# BMS_AFE_-_AFE.net
KiCad netlist of a schematic drawn in Altium Designer
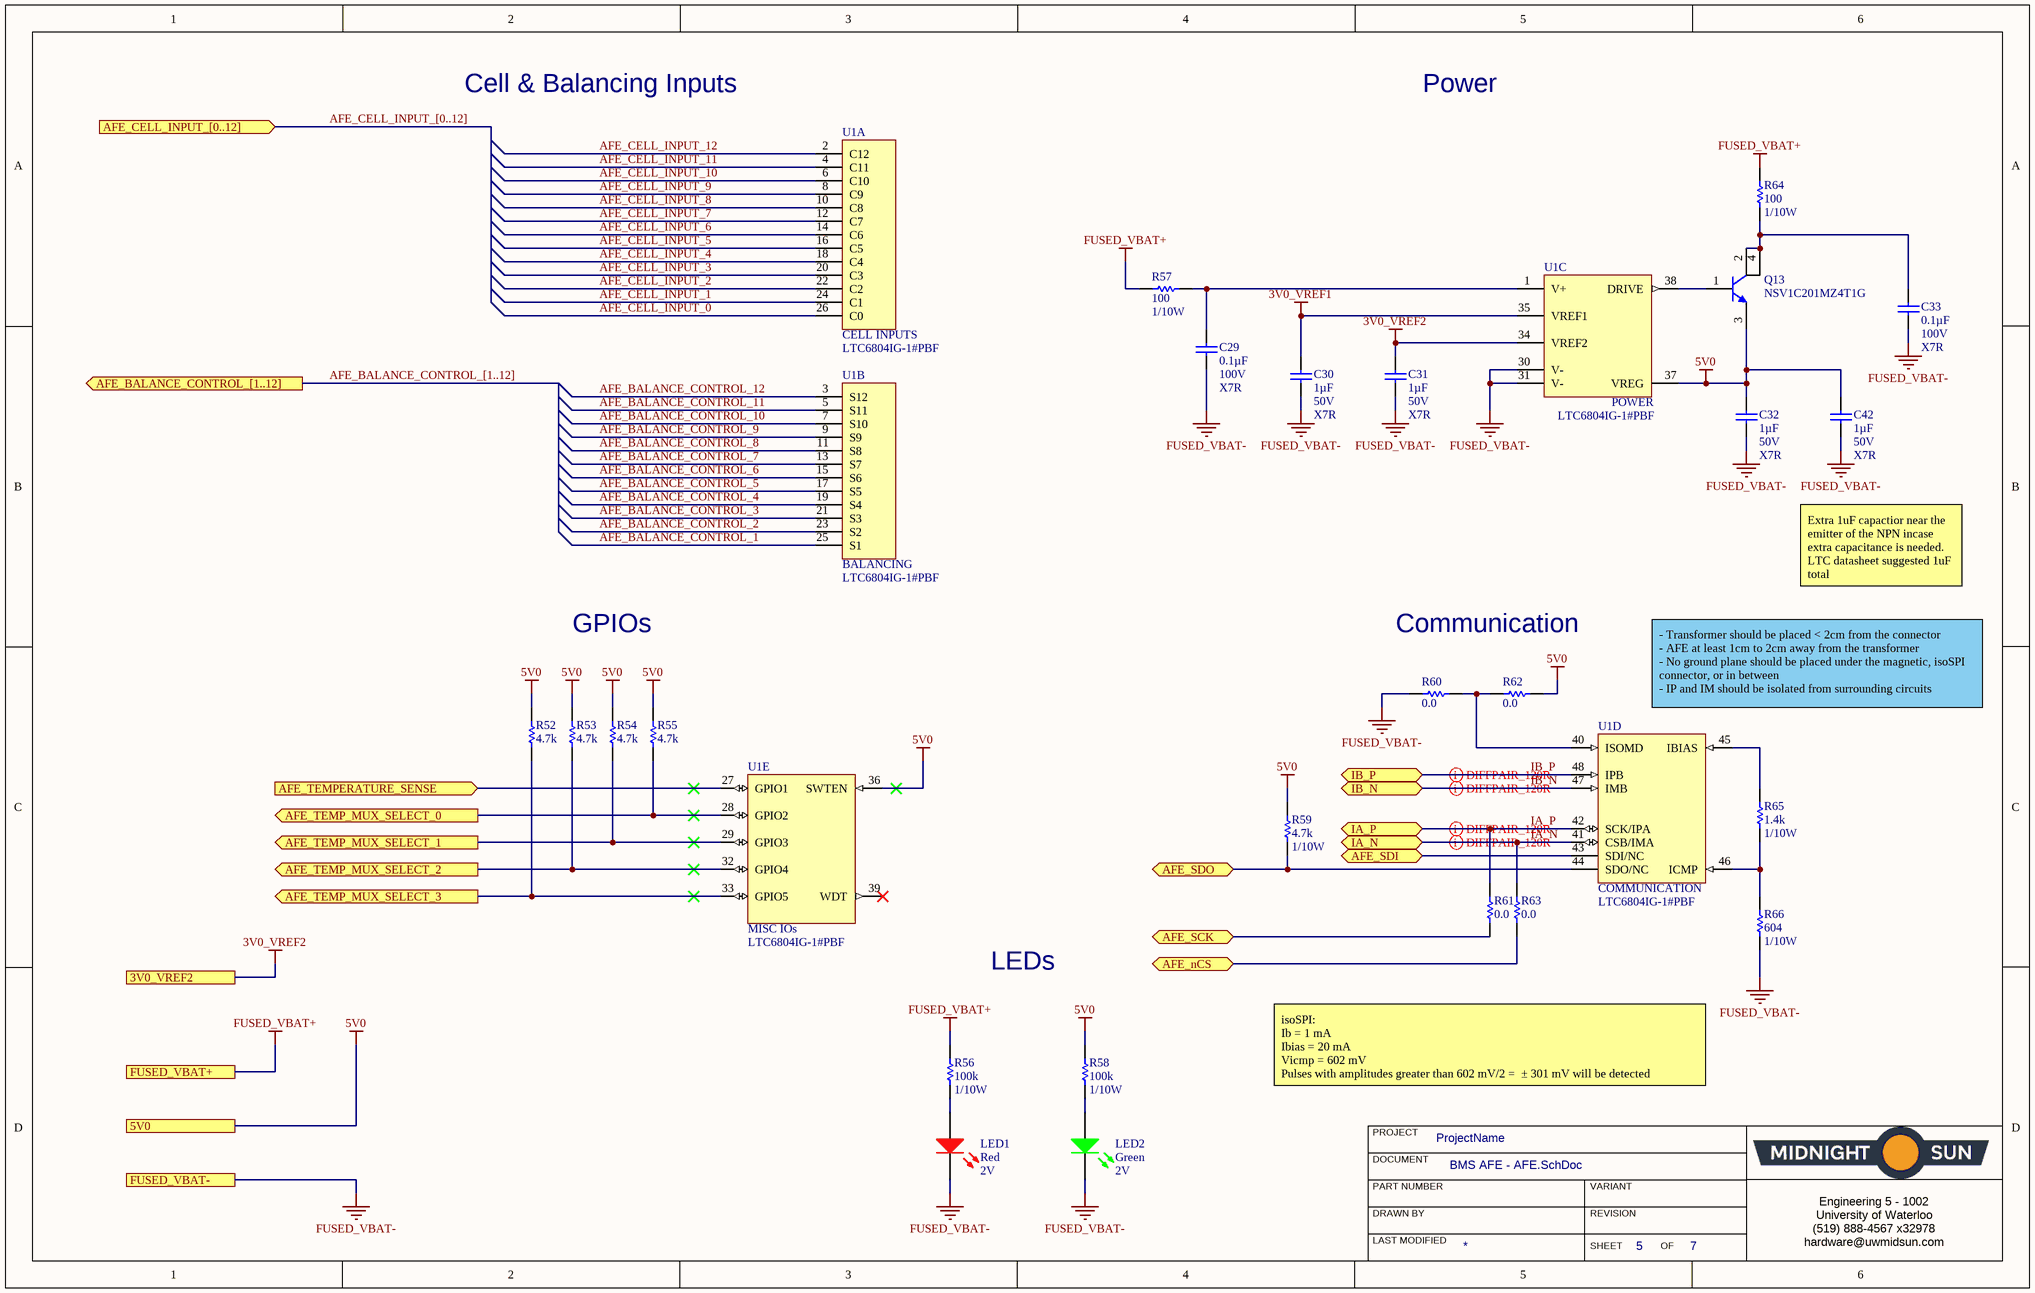
[diagram p0: BMS AFE - AFE.SchDoc]

(export (version "E")
  (design (tool "Eeschema 10.0.6"))
  (components
    (comp (ref "C29")
      (value "CAP CER 0.1UF 100V 10% X7R 0805")
      (footprint "CAP, 0805")
      (description "0.1µF ±10% 100V Ceramic Capacitor X7R 0805 (2012 Metric)")
      (fields
        (field (name "TOLERANCE") "±10%")
        (field (name "CAPACITANCE") "0.1µF")
        (field (name "VOLTAGE") "100V")
        (field (name "TEMPERATURE COEFFICIENT") "X7R")
      )
      (libsource (lib "Schematic Diagrams") (part "CAP CER 0.1UF 100V 10% X7R 0805"))
    )
    (comp (ref "C30")
      (value "CAP CER 1UF 50V 10% X7R 0603")
      (footprint "CAP, 0603")
      (description "1µF ±10% 50V Ceramic Capacitor X7R 0603 (1608 Metric)")
      (fields
        (field (name "TOLERANCE") "±10%")
        (field (name "CAPACITANCE") "1µF")
        (field (name "VOLTAGE") "50V")
        (field (name "TEMPERATURE COEFFICIENT") "X7R")
      )
      (libsource (lib "Schematic Diagrams") (part "CAP CER 1UF 50V 10% X7R 0603"))
    )
    (comp (ref "C31")
      (value "CAP CER 1UF 50V 10% X7R 0603")
      (footprint "CAP, 0603")
      (description "1µF ±10% 50V Ceramic Capacitor X7R 0603 (1608 Metric)")
      (fields
        (field (name "TOLERANCE") "±10%")
        (field (name "CAPACITANCE") "1µF")
        (field (name "VOLTAGE") "50V")
        (field (name "TEMPERATURE COEFFICIENT") "X7R")
      )
      (libsource (lib "Schematic Diagrams") (part "CAP CER 1UF 50V 10% X7R 0603"))
    )
    (comp (ref "C32")
      (value "CAP CER 1UF 50V 10% X7R 0603")
      (footprint "CAP, 0603")
      (description "1µF ±10% 50V Ceramic Capacitor X7R 0603 (1608 Metric)")
      (fields
        (field (name "TOLERANCE") "±10%")
        (field (name "CAPACITANCE") "1µF")
        (field (name "VOLTAGE") "50V")
        (field (name "TEMPERATURE COEFFICIENT") "X7R")
      )
      (libsource (lib "Schematic Diagrams") (part "CAP CER 1UF 50V 10% X7R 0603"))
    )
    (comp (ref "C33")
      (value "CAP CER 0.1UF 100V 10% X7R 0805")
      (footprint "CAP, 0805")
      (description "0.1µF ±10% 100V Ceramic Capacitor X7R 0805 (2012 Metric)")
      (fields
        (field (name "TOLERANCE") "±10%")
        (field (name "CAPACITANCE") "0.1µF")
        (field (name "VOLTAGE") "100V")
        (field (name "TEMPERATURE COEFFICIENT") "X7R")
      )
      (libsource (lib "Schematic Diagrams") (part "CAP CER 0.1UF 100V 10% X7R 0805"))
    )
    (comp (ref "C42")
      (value "CAP CER 1UF 50V 10% X7R 0603")
      (footprint "CAP, 0603")
      (description "1µF ±10% 50V Ceramic Capacitor X7R 0603 (1608 Metric)")
      (fields
        (field (name "TOLERANCE") "±10%")
        (field (name "CAPACITANCE") "1µF")
        (field (name "VOLTAGE") "50V")
        (field (name "TEMPERATURE COEFFICIENT") "X7R")
      )
      (libsource (lib "Schematic Diagrams") (part "CAP CER 1UF 50V 10% X7R 0603"))
    )
    (comp (ref "LED1")
      (value "LED RED CLEAR 2V 0603")
      (footprint "LED_0603")
      (description "Red 631nm LED Indication - Discrete 2V 0603 (1608 Metric)")
      (fields
        (field (name "MANUFACTURER") "Wurth Electronics Inc.")
        (field (name "MANUFACTURER PART NUMBER") "150060RS75000")
        (field (name "COLOR") "Red")
        (field (name "VOLTAGE - FORWARD (VF) (TYP)") "2V")
      )
      (libsource (lib "Schematic Diagrams") (part "LED RED CLEAR 2V 0603"))
    )
    (comp (ref "LED2")
      (value "LED GREEN CLEAR 2V 0603")
      (footprint "LED_0603")
      (description "Green 572nm LED Indication - Discrete 2V 0603 (1608 Metric)")
      (fields
        (field (name "MANUFACTURER") "Wurth Electronics Inc.")
        (field (name "MANUFACTURER PART NUMBER") "150060VS75000")
        (field (name "COLOR") "Green")
        (field (name "VOLTAGE - FORWARD (VF) (TYP)") "2V")
      )
      (libsource (lib "Schematic Diagrams") (part "LED GREEN CLEAR 2V 0603"))
    )
    (comp (ref "Q13")
      (value "NSV1C201MZ4T1G")
      (footprint "BJT NPN 100V 2A SOT223")
      (description "Bipolar (BJT) Transistor NPN 100V 2A 100MHz 800mW Surface Mount SOT-223 (TO-261)")
      (fields (field (name "MANUFACTURER") "ON Semiconductor"))
      (libsource (lib "Schematic Diagrams") (part "BJT NPN 100V 2A SOT223"))
    )
    (comp (ref "R52")
      (value "RES 4.7K OHM 1% 1/10W 0603")
      (footprint "RES, 0603")
      (description "4.7k Ohm ±1% 0.1W, 1/10W Chip Resistor 0603 (1608 Metric) Moisture Resistant Thick Film")
      (fields (field (name "TOLERANCE") "±1%") (field (name "RESISTANCE (OHMS)") "4.7k"))
      (libsource (lib "Schematic Diagrams") (part "RES 4.7K OHM 1% 1/10W 0603"))
    )
    (comp (ref "R53")
      (value "RES 4.7K OHM 1% 1/10W 0603")
      (footprint "RES, 0603")
      (description "4.7k Ohm ±1% 0.1W, 1/10W Chip Resistor 0603 (1608 Metric) Moisture Resistant Thick Film")
      (fields (field (name "TOLERANCE") "±1%") (field (name "RESISTANCE (OHMS)") "4.7k"))
      (libsource (lib "Schematic Diagrams") (part "RES 4.7K OHM 1% 1/10W 0603"))
    )
    (comp (ref "R54")
      (value "RES 4.7K OHM 1% 1/10W 0603")
      (footprint "RES, 0603")
      (description "4.7k Ohm ±1% 0.1W, 1/10W Chip Resistor 0603 (1608 Metric) Moisture Resistant Thick Film")
      (fields (field (name "TOLERANCE") "±1%") (field (name "RESISTANCE (OHMS)") "4.7k"))
      (libsource (lib "Schematic Diagrams") (part "RES 4.7K OHM 1% 1/10W 0603"))
    )
    (comp (ref "R55")
      (value "RES 4.7K OHM 1% 1/10W 0603")
      (footprint "RES, 0603")
      (description "4.7k Ohm ±1% 0.1W, 1/10W Chip Resistor 0603 (1608 Metric) Moisture Resistant Thick Film")
      (fields (field (name "TOLERANCE") "±1%") (field (name "RESISTANCE (OHMS)") "4.7k"))
      (libsource (lib "Schematic Diagrams") (part "RES 4.7K OHM 1% 1/10W 0603"))
    )
    (comp (ref "R56")
      (value "RES 100K OHM 5% 1/8W 0603")
      (footprint "RES, 0603")
      (description "RES SMD 100K OHM 5% 1/10W 0603")
      (fields
        (field (name "TOLERANCE") "±5%")
        (field (name "RESISTANCE") "100k")
        (field (name "POWER") "1/10W")
      )
      (libsource (lib "Schematic Diagrams") (part "RES 100K OHM 5% 1/8W 0603"))
    )
    (comp (ref "R57")
      (value "RES 100 OHM 1% 1/10W 0603")
      (footprint "RES, 0603")
      (description "100 Ohm ±1% 0.1W, 1/10W Chip Resistor 0603 (1608 Metric) Moisture Resistant Thick Film")
      (fields
        (field (name "TOLERANCE") "±1%")
        (field (name "RESISTANCE") "100")
        (field (name "POWER") "1/10W")
      )
      (libsource (lib "Schematic Diagrams") (part "RES 100 OHM 1% 1/10W 0603"))
    )
    (comp (ref "R58")
      (value "RES 100K OHM 5% 1/8W 0603")
      (footprint "RES, 0603")
      (description "RES SMD 100K OHM 5% 1/10W 0603")
      (fields
        (field (name "TOLERANCE") "±5%")
        (field (name "RESISTANCE") "100k")
        (field (name "POWER") "1/10W")
      )
      (libsource (lib "Schematic Diagrams") (part "RES 100K OHM 5% 1/8W 0603"))
    )
    (comp (ref "R59")
      (value "RES 4.7K OHM 1% 1/10W 0603")
      (footprint "RES, 0603")
      (description "4.7k Ohm ±1% 0.1W, 1/10W Chip Resistor 0603 (1608 Metric) Moisture Resistant Thick Film")
      (fields
        (field (name "TOLERANCE") "±1%")
        (field (name "RESISTANCE (OHMS)") "4.7k")
        (field (name "POWER (WATTS)") "1/10W")
      )
      (libsource (lib "Schematic Diagrams") (part "RES 4.7K OHM 1% 1/10W 0603"))
    )
    (comp (ref "R60")
      (value "RES 0.0 OHM 1/4W 0603")
      (footprint "RES, 0603")
      (description "RES SMD 0.0 OHM JUMPER 1/4W 0603")
      (fields (field (name "RESISTANCE") "0.0"))
      (libsource (lib "Schematic Diagrams") (part "RES 0.0 OHM 1/4W 0603"))
    )
    (comp (ref "R61")
      (value "RES 0.0 OHM 1/4W 0603")
      (footprint "RES, 0603")
      (description "RES SMD 0.0 OHM JUMPER 1/4W 0603")
      (fields (field (name "RESISTANCE") "0.0"))
      (libsource (lib "Schematic Diagrams") (part "RES 0.0 OHM 1/4W 0603"))
    )
    (comp (ref "R62")
      (value "RES 0.0 OHM 1/4W 0603")
      (footprint "RES, 0603")
      (description "RES SMD 0.0 OHM JUMPER 1/4W 0603")
      (fields (field (name "RESISTANCE") "0.0"))
      (libsource (lib "Schematic Diagrams") (part "RES 0.0 OHM 1/4W 0603"))
    )
    (comp (ref "R63")
      (value "RES 0.0 OHM 1/4W 0603")
      (footprint "RES, 0603")
      (description "RES SMD 0.0 OHM JUMPER 1/4W 0603")
      (fields (field (name "RESISTANCE") "0.0"))
      (libsource (lib "Schematic Diagrams") (part "RES 0.0 OHM 1/4W 0603"))
    )
    (comp (ref "R64")
      (value "RES 100 OHM 1% 1/10W 0603")
      (footprint "RES, 0603")
      (description "100 Ohm ±1% 0.1W, 1/10W Chip Resistor 0603 (1608 Metric) Moisture Resistant Thick Film")
      (fields
        (field (name "TOLERANCE") "±1%")
        (field (name "RESISTANCE") "100")
        (field (name "POWER") "1/10W")
      )
      (libsource (lib "Schematic Diagrams") (part "RES 100 OHM 1% 1/10W 0603"))
    )
    (comp (ref "R65")
      (value "RES 1.4k OHM 1% 1/10W 0603")
      (footprint "RES, 0603")
      (description "RES SMD 1.4K OHM 1% 1/10W 0603")
      (fields
        (field (name "TOLERANCE") "±1%")
        (field (name "RESISTANCE") "1.4k")
        (field (name "POWER") "1/10W")
      )
      (libsource (lib "Schematic Diagrams") (part "RES 1.4k OHM 1% 1/10W 0603"))
    )
    (comp (ref "R66")
      (value "RES 604 OHM 1% 1/10W 0603")
      (footprint "RES, 0603")
      (description "RES SMD 604 OHM 1% 1/10W 0603")
      (fields
        (field (name "TOLERANCE") "±1%")
        (field (name "RESISTANCE") "604")
        (field (name "POWER") "1/10W")
      )
      (libsource (lib "Schematic Diagrams") (part "RES 604 OHM 1% 1/10W 0603"))
    )
    (comp (ref "U1")
      (value "IC MONITOR BATT STACK 48SSOP")
      (footprint "SSOP50P780X200-48N")
      (description "Battery Battery Monitor IC Multi-Chemistry 48-SSOP")
      (fields (field (name "MANUFACTURER PART NUMBER 1") "LTC6804IG-1#PBF"))
      (libsource (lib "Schematic Diagrams") (part "IC MONITOR BATT STACK 48SSOP"))
    )
  )
  (nets
    (net (code "1") (name "/AFE_BALANCE_CONTROL_1") (class "Default")
      (node (ref "U1") (pin "25") (pinfunction "S1_25") (pintype "passive"))
    )
    (net (code "2") (name "/AFE_BALANCE_CONTROL_2") (class "Default")
      (node (ref "U1") (pin "23") (pinfunction "S2_23") (pintype "passive"))
    )
    (net (code "3") (name "/AFE_BALANCE_CONTROL_3") (class "Default")
      (node (ref "U1") (pin "21") (pinfunction "S3_21") (pintype "passive"))
    )
    (net (code "4") (name "/AFE_BALANCE_CONTROL_4") (class "Default")
      (node (ref "U1") (pin "19") (pinfunction "S4_19") (pintype "passive"))
    )
    (net (code "5") (name "/AFE_BALANCE_CONTROL_5") (class "Default")
      (node (ref "U1") (pin "17") (pinfunction "S5_17") (pintype "passive"))
    )
    (net (code "6") (name "/AFE_BALANCE_CONTROL_6") (class "Default")
      (node (ref "U1") (pin "15") (pinfunction "S6_15") (pintype "passive"))
    )
    (net (code "7") (name "/AFE_BALANCE_CONTROL_7") (class "Default")
      (node (ref "U1") (pin "13") (pinfunction "S7_13") (pintype "passive"))
    )
    (net (code "8") (name "/AFE_BALANCE_CONTROL_8") (class "Default")
      (node (ref "U1") (pin "11") (pinfunction "S8_11") (pintype "passive"))
    )
    (net (code "9") (name "/AFE_BALANCE_CONTROL_9") (class "Default")
      (node (ref "U1") (pin "9") (pinfunction "S9_9") (pintype "passive"))
    )
    (net (code "10") (name "/AFE_BALANCE_CONTROL_10") (class "Default")
      (node (ref "U1") (pin "7") (pinfunction "S10_7") (pintype "passive"))
    )
    (net (code "11") (name "/AFE_BALANCE_CONTROL_11") (class "Default")
      (node (ref "U1") (pin "5") (pinfunction "S11_5") (pintype "passive"))
    )
    (net (code "12") (name "/AFE_BALANCE_CONTROL_12") (class "Default")
      (node (ref "U1") (pin "3") (pinfunction "S12_3") (pintype "passive"))
    )
    (net (code "14") (name "/AFE_CELL_INPUT_0") (class "Default")
      (node (ref "U1") (pin "26") (pinfunction "C0_26") (pintype "passive"))
    )
    (net (code "15") (name "/AFE_CELL_INPUT_1") (class "Default")
      (node (ref "U1") (pin "24") (pinfunction "C1_24") (pintype "passive"))
    )
    (net (code "16") (name "/AFE_CELL_INPUT_2") (class "Default")
      (node (ref "U1") (pin "22") (pinfunction "C2_22") (pintype "passive"))
    )
    (net (code "17") (name "/AFE_CELL_INPUT_3") (class "Default")
      (node (ref "U1") (pin "20") (pinfunction "C3_20") (pintype "passive"))
    )
    (net (code "18") (name "/AFE_CELL_INPUT_4") (class "Default")
      (node (ref "U1") (pin "18") (pinfunction "C4_18") (pintype "passive"))
    )
    (net (code "19") (name "/AFE_CELL_INPUT_5") (class "Default")
      (node (ref "U1") (pin "16") (pinfunction "C5_16") (pintype "passive"))
    )
    (net (code "20") (name "/AFE_CELL_INPUT_6") (class "Default")
      (node (ref "U1") (pin "14") (pinfunction "C6_14") (pintype "passive"))
    )
    (net (code "21") (name "/AFE_CELL_INPUT_7") (class "Default")
      (node (ref "U1") (pin "12") (pinfunction "C7_12") (pintype "passive"))
    )
    (net (code "22") (name "/AFE_CELL_INPUT_8") (class "Default")
      (node (ref "U1") (pin "10") (pinfunction "C8_10") (pintype "passive"))
    )
    (net (code "23") (name "/AFE_CELL_INPUT_9") (class "Default")
      (node (ref "U1") (pin "8") (pinfunction "C9_8") (pintype "passive"))
    )
    (net (code "24") (name "/AFE_CELL_INPUT_10") (class "Default")
      (node (ref "U1") (pin "6") (pinfunction "C10_6") (pintype "passive"))
    )
    (net (code "25") (name "/AFE_CELL_INPUT_11") (class "Default")
      (node (ref "U1") (pin "4") (pinfunction "C11_4") (pintype "passive"))
    )
    (net (code "26") (name "/AFE_CELL_INPUT_12") (class "Default")
      (node (ref "U1") (pin "2") (pinfunction "C12_2") (pintype "passive"))
    )
    (net (code "28") (name "/AFE_SCK") (class "Default")
      (node (ref "R61") (pin "2") (pinfunction "2_2") (pintype "passive"))
    )
    (net (code "29") (name "/AFE_SDI") (class "Default")
      (node (ref "U1") (pin "43") (pinfunction "SDI/NC_43") (pintype "passive"))
    )
    (net (code "30") (name "/AFE_SDO") (class "Default")
      (node (ref "R59") (pin "2") (pinfunction "2_2") (pintype "passive"))
      (node (ref "U1") (pin "44") (pinfunction "SDO/NC_44") (pintype "passive"))
    )
    (net (code "31") (name "/AFE_TEMPERATURE_SENSE") (class "Default")
      (node (ref "U1") (pin "27") (pinfunction "GPIO1_27") (pintype "bidirectional"))
    )
    (net (code "32") (name "/AFE_TEMP_MUX_SELECT_0") (class "Default")
      (node (ref "R55") (pin "1") (pinfunction "1_1") (pintype "passive"))
      (node (ref "U1") (pin "28") (pinfunction "GPIO2_28") (pintype "bidirectional"))
    )
    (net (code "33") (name "/AFE_TEMP_MUX_SELECT_1") (class "Default")
      (node (ref "R54") (pin "1") (pinfunction "1_1") (pintype "passive"))
      (node (ref "U1") (pin "29") (pinfunction "GPIO3_29") (pintype "bidirectional"))
    )
    (net (code "34") (name "/AFE_TEMP_MUX_SELECT_2") (class "Default")
      (node (ref "R53") (pin "1") (pinfunction "1_1") (pintype "passive"))
      (node (ref "U1") (pin "32") (pinfunction "GPIO4_32") (pintype "bidirectional"))
    )
    (net (code "35") (name "/AFE_TEMP_MUX_SELECT_3") (class "Default")
      (node (ref "R52") (pin "1") (pinfunction "1_1") (pintype "passive"))
      (node (ref "U1") (pin "33") (pinfunction "GPIO5_33") (pintype "bidirectional"))
    )
    (net (code "36") (name "/AFE_nCS") (class "Default")
      (node (ref "R63") (pin "2") (pinfunction "2_2") (pintype "passive"))
    )
    (net (code "37") (name "/IA_N") (class "Default")
      (node (ref "R63") (pin "1") (pinfunction "1_1") (pintype "passive"))
      (node (ref "U1") (pin "41") (pinfunction "CSB/IMA_41") (pintype "bidirectional"))
    )
    (net (code "38") (name "/IA_P") (class "Default")
      (node (ref "R61") (pin "1") (pinfunction "1_1") (pintype "passive"))
      (node (ref "U1") (pin "42") (pinfunction "SCK/IPA_42") (pintype "bidirectional"))
    )
    (net (code "39") (name "/IB_N") (class "Default")
      (node (ref "U1") (pin "47") (pinfunction "IMB_47") (pintype "input"))
    )
    (net (code "40") (name "/IB_P") (class "Default")
      (node (ref "U1") (pin "48") (pinfunction "IPB_48") (pintype "input"))
    )
    (net (code "41") (name "3V0_VREF1") (class "Default")
      (node (ref "C30") (pin "1") (pinfunction "1_1") (pintype "passive"))
      (node (ref "U1") (pin "35") (pinfunction "VREF1_35") (pintype "power_in"))
    )
    (net (code "42") (name "3V0_VREF2") (class "Default")
      (node (ref "C31") (pin "1") (pinfunction "1_1") (pintype "passive"))
      (node (ref "U1") (pin "34") (pinfunction "VREF2_34") (pintype "power_in"))
    )
    (net (code "43") (name "5V0") (class "Default")
      (node (ref "C32") (pin "1") (pinfunction "1_1") (pintype "passive"))
      (node (ref "C42") (pin "1") (pinfunction "1_1") (pintype "passive"))
      (node (ref "Q13") (pin "3") (pinfunction "E_3") (pintype "passive"))
      (node (ref "R52") (pin "2") (pinfunction "2_2") (pintype "passive"))
      (node (ref "R53") (pin "2") (pinfunction "2_2") (pintype "passive"))
      (node (ref "R54") (pin "2") (pinfunction "2_2") (pintype "passive"))
      (node (ref "R55") (pin "2") (pinfunction "2_2") (pintype "passive"))
      (node (ref "R58") (pin "1") (pinfunction "1_1") (pintype "passive"))
      (node (ref "R59") (pin "1") (pinfunction "1_1") (pintype "passive"))
      (node (ref "R62") (pin "2") (pinfunction "2_2") (pintype "passive"))
      (node (ref "U1") (pin "36") (pinfunction "SWTEN_36") (pintype "input"))
      (node (ref "U1") (pin "37") (pinfunction "VREG_37") (pintype "power_in"))
    )
    (net (code "44") (name "FUSED_VBAT+") (class "Default")
      (node (ref "R56") (pin "1") (pinfunction "1_1") (pintype "passive"))
      (node (ref "R57") (pin "1") (pinfunction "1_1") (pintype "passive"))
      (node (ref "R64") (pin "2") (pinfunction "2_2") (pintype "passive"))
    )
    (net (code "45") (name "FUSED_VBAT-") (class "Default")
      (node (ref "C29") (pin "2") (pinfunction "2_2") (pintype "passive"))
      (node (ref "C30") (pin "2") (pinfunction "2_2") (pintype "passive"))
      (node (ref "C31") (pin "2") (pinfunction "2_2") (pintype "passive"))
      (node (ref "C32") (pin "2") (pinfunction "2_2") (pintype "passive"))
      (node (ref "C33") (pin "2") (pinfunction "2_2") (pintype "passive"))
      (node (ref "C42") (pin "2") (pinfunction "2_2") (pintype "passive"))
      (node (ref "LED1") (pin "2") (pinfunction "K_2") (pintype "passive"))
      (node (ref "LED2") (pin "2") (pinfunction "K_2") (pintype "passive"))
      (node (ref "R60") (pin "1") (pinfunction "1_1") (pintype "passive"))
      (node (ref "R66") (pin "2") (pinfunction "2_2") (pintype "passive"))
      (node (ref "U1") (pin "30") (pinfunction "V-_30") (pintype "power_in"))
      (node (ref "U1") (pin "31") (pinfunction "V-_31") (pintype "power_in"))
    )
    (net (code "46") (name "Net-(C33-Pad1)") (class "Default")
      (node (ref "C33") (pin "1") (pinfunction "1_1") (pintype "passive"))
      (node (ref "Q13") (pin "2") (pinfunction "C_2") (pintype "passive"))
      (node (ref "Q13") (pin "4") (pinfunction "C_4") (pintype "passive"))
      (node (ref "R64") (pin "1") (pinfunction "1_1") (pintype "passive"))
    )
    (net (code "47") (name "Net-(LED1-A)") (class "Default")
      (node (ref "LED1") (pin "1") (pinfunction "A_1") (pintype "passive"))
      (node (ref "R56") (pin "2") (pinfunction "2_2") (pintype "passive"))
    )
    (net (code "48") (name "Net-(LED2-A)") (class "Default")
      (node (ref "LED2") (pin "1") (pinfunction "A_1") (pintype "passive"))
      (node (ref "R58") (pin "2") (pinfunction "2_2") (pintype "passive"))
    )
    (net (code "49") (name "Net-(Q13-B)") (class "Default")
      (node (ref "Q13") (pin "1") (pinfunction "B_1") (pintype "passive"))
      (node (ref "U1") (pin "38") (pinfunction "DRIVE_38") (pintype "output"))
    )
    (net (code "50") (name "Net-(U1C-V+)") (class "Default")
      (node (ref "C29") (pin "1") (pinfunction "1_1") (pintype "passive"))
      (node (ref "R57") (pin "2") (pinfunction "2_2") (pintype "passive"))
      (node (ref "U1") (pin "1") (pinfunction "V+_1") (pintype "power_in"))
    )
    (net (code "51") (name "Net-(U1D-IBIAS)") (class "Default")
      (node (ref "R65") (pin "1") (pinfunction "1_1") (pintype "passive"))
      (node (ref "U1") (pin "45") (pinfunction "IBIAS_45") (pintype "input"))
    )
    (net (code "52") (name "Net-(U1D-ICMP)") (class "Default")
      (node (ref "R65") (pin "2") (pinfunction "2_2") (pintype "passive"))
      (node (ref "R66") (pin "1") (pinfunction "1_1") (pintype "passive"))
      (node (ref "U1") (pin "46") (pinfunction "ICMP_46") (pintype "input"))
    )
    (net (code "53") (name "Net-(U1D-ISOMD)") (class "Default")
      (node (ref "R60") (pin "2") (pinfunction "2_2") (pintype "passive"))
      (node (ref "R62") (pin "1") (pinfunction "1_1") (pintype "passive"))
      (node (ref "U1") (pin "40") (pinfunction "ISOMD_40") (pintype "input"))
    )
    (net (code "54") (name "unconnected-(U1E-WDT-Pad39)") (class "Default")
      (node (ref "U1") (pin "39") (pinfunction "WDT_39") (pintype "output+no_connect"))
    )
  )
)
